# Charlieplex_5x4.net
KiCad netlist of a schematic drawn in EAGLE
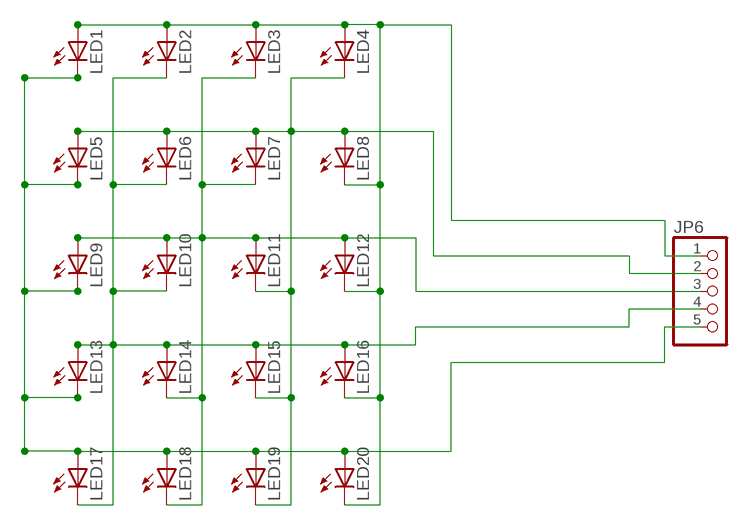
[diagram p0: schematic, sheet 1]

(export (version "E")
  (design (tool "Eeschema 10.0.6"))
  (components
    (comp (ref "JP6")
      (value "PINHD-1X5")
      (footprint "eagle-import:1X05")
      (libsource (lib "eagle-import") (part "PINHD-1X5"))
    )
    (comp (ref "LED1")
      (value "LED3MM")
      (footprint "eagle-import:LED3MM")
      (libsource (lib "eagle-import") (part "LED3MM"))
    )
    (comp (ref "LED2")
      (value "LED3MM")
      (footprint "eagle-import:LED3MM")
      (libsource (lib "eagle-import") (part "LED3MM"))
    )
    (comp (ref "LED3")
      (value "LED3MM")
      (footprint "eagle-import:LED3MM")
      (libsource (lib "eagle-import") (part "LED3MM"))
    )
    (comp (ref "LED4")
      (value "LED3MM")
      (footprint "eagle-import:LED3MM")
      (libsource (lib "eagle-import") (part "LED3MM"))
    )
    (comp (ref "LED5")
      (value "LED3MM")
      (footprint "eagle-import:LED3MM")
      (libsource (lib "eagle-import") (part "LED3MM"))
    )
    (comp (ref "LED6")
      (value "LED3MM")
      (footprint "eagle-import:LED3MM")
      (libsource (lib "eagle-import") (part "LED3MM"))
    )
    (comp (ref "LED7")
      (value "LED3MM")
      (footprint "eagle-import:LED3MM")
      (libsource (lib "eagle-import") (part "LED3MM"))
    )
    (comp (ref "LED8")
      (value "LED3MM")
      (footprint "eagle-import:LED3MM")
      (libsource (lib "eagle-import") (part "LED3MM"))
    )
    (comp (ref "LED9")
      (value "LED3MM")
      (footprint "eagle-import:LED3MM")
      (libsource (lib "eagle-import") (part "LED3MM"))
    )
    (comp (ref "LED10")
      (value "LED3MM")
      (footprint "eagle-import:LED3MM")
      (libsource (lib "eagle-import") (part "LED3MM"))
    )
    (comp (ref "LED11")
      (value "LED3MM")
      (footprint "eagle-import:LED3MM")
      (libsource (lib "eagle-import") (part "LED3MM"))
    )
    (comp (ref "LED12")
      (value "LED3MM")
      (footprint "eagle-import:LED3MM")
      (libsource (lib "eagle-import") (part "LED3MM"))
    )
    (comp (ref "LED13")
      (value "LED3MM")
      (footprint "eagle-import:LED3MM")
      (libsource (lib "eagle-import") (part "LED3MM"))
    )
    (comp (ref "LED14")
      (value "LED3MM")
      (footprint "eagle-import:LED3MM")
      (libsource (lib "eagle-import") (part "LED3MM"))
    )
    (comp (ref "LED15")
      (value "LED3MM")
      (footprint "eagle-import:LED3MM")
      (libsource (lib "eagle-import") (part "LED3MM"))
    )
    (comp (ref "LED16")
      (value "LED3MM")
      (footprint "eagle-import:LED3MM")
      (libsource (lib "eagle-import") (part "LED3MM"))
    )
    (comp (ref "LED17")
      (value "LED3MM")
      (footprint "eagle-import:LED3MM")
      (libsource (lib "eagle-import") (part "LED3MM"))
    )
    (comp (ref "LED18")
      (value "LED3MM")
      (footprint "eagle-import:LED3MM")
      (libsource (lib "eagle-import") (part "LED3MM"))
    )
    (comp (ref "LED19")
      (value "LED3MM")
      (footprint "eagle-import:LED3MM")
      (libsource (lib "eagle-import") (part "LED3MM"))
    )
    (comp (ref "LED20")
      (value "LED3MM")
      (footprint "eagle-import:LED3MM")
      (libsource (lib "eagle-import") (part "LED3MM"))
    )
  )
  (nets
    (net (code "1") (name "Net-(LED1-C)") (class "Default")
      (node (ref "JP6") (pin "5") (pinfunction "5_5") (pintype "passive"))
      (node (ref "LED1") (pin "K") (pinfunction "C_K") (pintype "passive"))
      (node (ref "LED13") (pin "K") (pinfunction "C_K") (pintype "passive"))
      (node (ref "LED17") (pin "A") (pinfunction "A_A") (pintype "passive"))
      (node (ref "LED18") (pin "A") (pinfunction "A_A") (pintype "passive"))
      (node (ref "LED19") (pin "A") (pinfunction "A_A") (pintype "passive"))
      (node (ref "LED20") (pin "A") (pinfunction "A_A") (pintype "passive"))
      (node (ref "LED5") (pin "K") (pinfunction "C_K") (pintype "passive"))
      (node (ref "LED9") (pin "K") (pinfunction "C_K") (pintype "passive"))
    )
    (net (code "2") (name "Net-(LED10-C)") (class "Default")
      (node (ref "JP6") (pin "4") (pinfunction "4_4") (pintype "passive"))
      (node (ref "LED10") (pin "K") (pinfunction "C_K") (pintype "passive"))
      (node (ref "LED13") (pin "A") (pinfunction "A_A") (pintype "passive"))
      (node (ref "LED14") (pin "A") (pinfunction "A_A") (pintype "passive"))
      (node (ref "LED15") (pin "A") (pinfunction "A_A") (pintype "passive"))
      (node (ref "LED16") (pin "A") (pinfunction "A_A") (pintype "passive"))
      (node (ref "LED17") (pin "K") (pinfunction "C_K") (pintype "passive"))
      (node (ref "LED2") (pin "K") (pinfunction "C_K") (pintype "passive"))
      (node (ref "LED6") (pin "K") (pinfunction "C_K") (pintype "passive"))
    )
    (net (code "3") (name "Net-(LED11-C)") (class "Default")
      (node (ref "JP6") (pin "2") (pinfunction "2_2") (pintype "passive"))
      (node (ref "LED11") (pin "K") (pinfunction "C_K") (pintype "passive"))
      (node (ref "LED15") (pin "K") (pinfunction "C_K") (pintype "passive"))
      (node (ref "LED19") (pin "K") (pinfunction "C_K") (pintype "passive"))
      (node (ref "LED4") (pin "K") (pinfunction "C_K") (pintype "passive"))
      (node (ref "LED5") (pin "A") (pinfunction "A_A") (pintype "passive"))
      (node (ref "LED6") (pin "A") (pinfunction "A_A") (pintype "passive"))
      (node (ref "LED7") (pin "A") (pinfunction "A_A") (pintype "passive"))
      (node (ref "LED8") (pin "A") (pinfunction "A_A") (pintype "passive"))
    )
    (net (code "4") (name "Net-(LED12-C)") (class "Default")
      (node (ref "JP6") (pin "1") (pinfunction "1_1") (pintype "passive"))
      (node (ref "LED1") (pin "A") (pinfunction "A_A") (pintype "passive"))
      (node (ref "LED12") (pin "K") (pinfunction "C_K") (pintype "passive"))
      (node (ref "LED16") (pin "K") (pinfunction "C_K") (pintype "passive"))
      (node (ref "LED2") (pin "A") (pinfunction "A_A") (pintype "passive"))
      (node (ref "LED20") (pin "K") (pinfunction "C_K") (pintype "passive"))
      (node (ref "LED3") (pin "A") (pinfunction "A_A") (pintype "passive"))
      (node (ref "LED4") (pin "A") (pinfunction "A_A") (pintype "passive"))
      (node (ref "LED8") (pin "K") (pinfunction "C_K") (pintype "passive"))
    )
    (net (code "5") (name "Net-(LED14-C)") (class "Default")
      (node (ref "JP6") (pin "3") (pinfunction "3_3") (pintype "passive"))
      (node (ref "LED10") (pin "A") (pinfunction "A_A") (pintype "passive"))
      (node (ref "LED11") (pin "A") (pinfunction "A_A") (pintype "passive"))
      (node (ref "LED12") (pin "A") (pinfunction "A_A") (pintype "passive"))
      (node (ref "LED14") (pin "K") (pinfunction "C_K") (pintype "passive"))
      (node (ref "LED18") (pin "K") (pinfunction "C_K") (pintype "passive"))
      (node (ref "LED3") (pin "K") (pinfunction "C_K") (pintype "passive"))
      (node (ref "LED7") (pin "K") (pinfunction "C_K") (pintype "passive"))
      (node (ref "LED9") (pin "A") (pinfunction "A_A") (pintype "passive"))
    )
  )
)
